# ip_phone_d_lcd_keyboard.net
KiCad netlist of a schematic drawn in Altium Designer
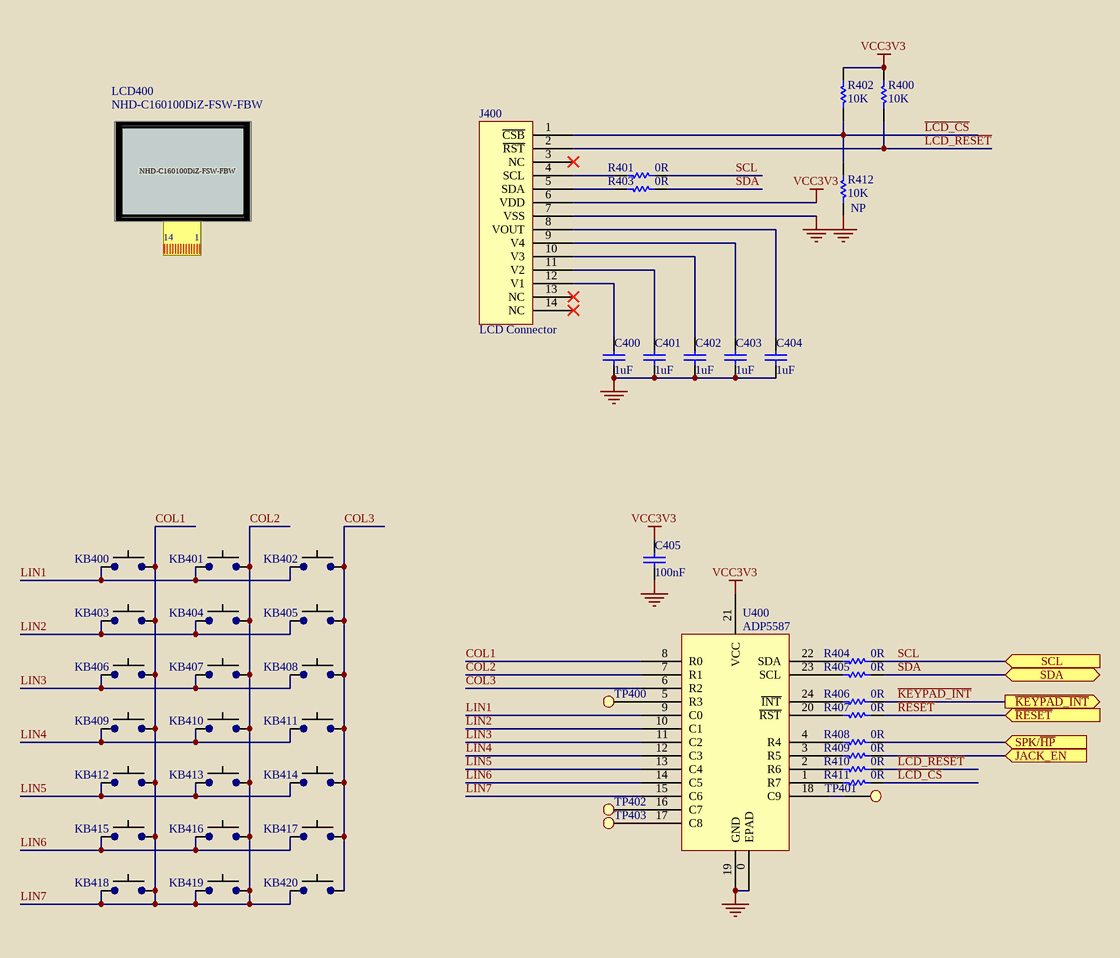
[diagram p0: ip_phone_d_lcd_keyboard.SchDoc]

(export (version "E")
  (design (tool "Eeschema 10.0.6"))
  (components
    (comp (ref "C400")
      (value "1uF")
      (footprint "ip_phone:CC1005-0402")
      (description "CAP CER 1.0UF 6.3V 20% X5R 0402")
      (fields
        (field (name "EVENDORPART#") "490-1319-1-ND")
        (field (name "MANUFACTURER") "Murata Electronics North America")
      )
      (libsource (lib "ip_phone") (part "Capacitor"))
    )
    (comp (ref "C401")
      (value "1uF")
      (footprint "ip_phone:CC1005-0402")
      (description "CAP CER 1.0UF 6.3V 20% X5R 0402")
      (fields
        (field (name "EVENDORPART#") "490-1319-1-ND")
        (field (name "MANUFACTURER") "Murata Electronics North America")
      )
      (libsource (lib "ip_phone") (part "Capacitor"))
    )
    (comp (ref "C402")
      (value "1uF")
      (footprint "ip_phone:CC1005-0402")
      (description "CAP CER 1.0UF 6.3V 20% X5R 0402")
      (fields
        (field (name "EVENDORPART#") "490-1319-1-ND")
        (field (name "MANUFACTURER") "Murata Electronics North America")
      )
      (libsource (lib "ip_phone") (part "Capacitor"))
    )
    (comp (ref "C403")
      (value "1uF")
      (footprint "ip_phone:CC1005-0402")
      (description "CAP CER 1.0UF 6.3V 20% X5R 0402")
      (fields
        (field (name "EVENDORPART#") "490-1319-1-ND")
        (field (name "MANUFACTURER") "Murata Electronics North America")
      )
      (libsource (lib "ip_phone") (part "Capacitor"))
    )
    (comp (ref "C404")
      (value "1uF")
      (footprint "ip_phone:CC1005-0402")
      (description "CAP CER 1.0UF 6.3V 20% X5R 0402")
      (fields
        (field (name "EVENDORPART#") "490-1319-1-ND")
        (field (name "MANUFACTURER") "Murata Electronics North America")
      )
      (libsource (lib "ip_phone") (part "Capacitor"))
    )
    (comp (ref "C405")
      (value "100nF")
      (footprint "ip_phone:CC1005-0402")
      (description "MLCC - SMD/SMT 0.1UF 16V 10% 0402")
      (fields (field (name "EVENDORPART#") "810-C1005X7R1C104K") (field (name "MANUFACTURER") "TDK"))
      (libsource (lib "ip_phone") (part "Capacitor"))
    )
    (comp (ref "J400")
      (value "LCD Connector")
      (footprint "ip_phone:LCD_Connector")
      (fields
        (field (name "EVENDORPART#") "538-52892-1495")
        (field (name "MANUFACTURER") "Molex")
        (field (name "PART#") "52892-1495")
      )
      (libsource (lib "ip_phone") (part "LCD Connector"))
    )
    (comp (ref "KB400")
      (value "Keypad_Button")
      (footprint "ip_phone:Keypad_Button")
      (libsource (lib "ip_phone") (part "Keypad_Button"))
    )
    (comp (ref "KB401")
      (value "Keypad_Button")
      (footprint "ip_phone:Keypad_Button")
      (libsource (lib "ip_phone") (part "Keypad_Button"))
    )
    (comp (ref "KB402")
      (value "Keypad_Button")
      (footprint "ip_phone:Keypad_Button")
      (libsource (lib "ip_phone") (part "Keypad_Button"))
    )
    (comp (ref "KB403")
      (value "Keypad_Button")
      (footprint "ip_phone:Keypad_Button")
      (libsource (lib "ip_phone") (part "Keypad_Button"))
    )
    (comp (ref "KB404")
      (value "Keypad_Button")
      (footprint "ip_phone:Keypad_Button")
      (libsource (lib "ip_phone") (part "Keypad_Button"))
    )
    (comp (ref "KB405")
      (value "Keypad_Button")
      (footprint "ip_phone:Keypad_Button")
      (libsource (lib "ip_phone") (part "Keypad_Button"))
    )
    (comp (ref "KB406")
      (value "Keypad_Button")
      (footprint "ip_phone:Keypad_Button")
      (libsource (lib "ip_phone") (part "Keypad_Button"))
    )
    (comp (ref "KB407")
      (value "Keypad_Button")
      (footprint "ip_phone:Keypad_Button")
      (libsource (lib "ip_phone") (part "Keypad_Button"))
    )
    (comp (ref "KB408")
      (value "Keypad_Button")
      (footprint "ip_phone:Keypad_Button")
      (libsource (lib "ip_phone") (part "Keypad_Button"))
    )
    (comp (ref "KB409")
      (value "Keypad_Button")
      (footprint "ip_phone:Keypad_Button")
      (libsource (lib "ip_phone") (part "Keypad_Button"))
    )
    (comp (ref "KB410")
      (value "Keypad_Button")
      (footprint "ip_phone:Keypad_Button")
      (libsource (lib "ip_phone") (part "Keypad_Button"))
    )
    (comp (ref "KB411")
      (value "Keypad_Button")
      (footprint "ip_phone:Keypad_Button")
      (libsource (lib "ip_phone") (part "Keypad_Button"))
    )
    (comp (ref "KB412")
      (value "Keypad_Button")
      (footprint "ip_phone:Keypad_Button")
      (libsource (lib "ip_phone") (part "Keypad_Button"))
    )
    (comp (ref "KB413")
      (value "Keypad_Button")
      (footprint "ip_phone:Keypad_Button")
      (libsource (lib "ip_phone") (part "Keypad_Button"))
    )
    (comp (ref "KB414")
      (value "Keypad_Button")
      (footprint "ip_phone:Keypad_Button")
      (libsource (lib "ip_phone") (part "Keypad_Button"))
    )
    (comp (ref "KB415")
      (value "Keypad_Button")
      (footprint "ip_phone:Keypad_Button")
      (libsource (lib "ip_phone") (part "Keypad_Button"))
    )
    (comp (ref "KB416")
      (value "Keypad_Button")
      (footprint "ip_phone:Keypad_Button")
      (libsource (lib "ip_phone") (part "Keypad_Button"))
    )
    (comp (ref "KB417")
      (value "Keypad_Button")
      (footprint "ip_phone:Keypad_Button")
      (libsource (lib "ip_phone") (part "Keypad_Button"))
    )
    (comp (ref "KB418")
      (value "Keypad_Button")
      (footprint "ip_phone:Keypad_Button")
      (libsource (lib "ip_phone") (part "Keypad_Button"))
    )
    (comp (ref "KB419")
      (value "Keypad_Button")
      (footprint "ip_phone:Keypad_Button")
      (libsource (lib "ip_phone") (part "Keypad_Button"))
    )
    (comp (ref "KB420")
      (value "Keypad_Button")
      (footprint "ip_phone:Keypad_Button")
      (libsource (lib "ip_phone") (part "Keypad_Button"))
    )
    (comp (ref "LCD400")
      (value "NHD-C160100DiZ-FSW-FBW")
      (description "LCD")
      (fields
        (field (name "EVENDORPART#") "763-C160100DIZFSWFBW")
        (field (name "MANUFACTURER") "Newhaven Display")
      )
      (libsource (lib "ip_phone") (part "LCD"))
    )
    (comp (ref "R400")
      (value "10K")
      (footprint "ip_phone:CR1005-0402")
      (description "Thick Film Resistors SMD 0402 10K 5%  1/16 W")
      (fields (field (name "EVENDORPART#") "311-10KJRCT-ND") (field (name "MANUFACTURER") "Yageo"))
      (libsource (lib "ip_phone") (part "Resistor"))
    )
    (comp (ref "R401")
      (value "0R")
      (footprint "ip_phone:CR1005-0402")
      (description "Thick Film Resistors 0402 1/16W Jumper")
      (fields
        (field (name "EVENDORPART#") "667-ERJ-2GE0R00X")
        (field (name "MANUFACTURER") "Panasonic Electronic Components")
      )
      (libsource (lib "ip_phone") (part "Resistor"))
    )
    (comp (ref "R402")
      (value "10K")
      (footprint "ip_phone:CR1005-0402")
      (description "Thick Film Resistors SMD 0402 10K 5%  1/16 W")
      (fields (field (name "EVENDORPART#") "311-10KJRCT-ND") (field (name "MANUFACTURER") "Yageo"))
      (libsource (lib "ip_phone") (part "Resistor"))
    )
    (comp (ref "R403")
      (value "0R")
      (footprint "ip_phone:CR1005-0402")
      (description "Thick Film Resistors 0402 1/16W Jumper")
      (fields
        (field (name "EVENDORPART#") "667-ERJ-2GE0R00X")
        (field (name "MANUFACTURER") "Panasonic Electronic Components")
      )
      (libsource (lib "ip_phone") (part "Resistor"))
    )
    (comp (ref "R404")
      (value "0R")
      (footprint "ip_phone:CR1005-0402")
      (description "Thick Film Resistors 0402 1/16W Jumper")
      (fields
        (field (name "EVENDORPART#") "667-ERJ-2GE0R00X")
        (field (name "MANUFACTURER") "Panasonic Electronic Components")
      )
      (libsource (lib "ip_phone") (part "Resistor"))
    )
    (comp (ref "R405")
      (value "0R")
      (footprint "ip_phone:CR1005-0402")
      (description "Thick Film Resistors 0402 1/16W Jumper")
      (fields
        (field (name "EVENDORPART#") "667-ERJ-2GE0R00X")
        (field (name "MANUFACTURER") "Panasonic Electronic Components")
      )
      (libsource (lib "ip_phone") (part "Resistor"))
    )
    (comp (ref "R406")
      (value "0R")
      (footprint "ip_phone:CR1005-0402")
      (description "Thick Film Resistors 0402 1/16W Jumper")
      (fields
        (field (name "EVENDORPART#") "667-ERJ-2GE0R00X")
        (field (name "MANUFACTURER") "Panasonic Electronic Components")
      )
      (libsource (lib "ip_phone") (part "Resistor"))
    )
    (comp (ref "R407")
      (value "0R")
      (footprint "ip_phone:CR1005-0402")
      (description "Thick Film Resistors 0402 1/16W Jumper")
      (fields
        (field (name "EVENDORPART#") "667-ERJ-2GE0R00X")
        (field (name "MANUFACTURER") "Panasonic Electronic Components")
      )
      (libsource (lib "ip_phone") (part "Resistor"))
    )
    (comp (ref "R408")
      (value "0R")
      (footprint "ip_phone:CR1005-0402")
      (description "Thick Film Resistors 0402 1/16W Jumper")
      (fields
        (field (name "EVENDORPART#") "667-ERJ-2GE0R00X")
        (field (name "MANUFACTURER") "Panasonic Electronic Components")
      )
      (libsource (lib "ip_phone") (part "Resistor"))
    )
    (comp (ref "R409")
      (value "0R")
      (footprint "ip_phone:CR1005-0402")
      (description "Thick Film Resistors 0402 1/16W Jumper")
      (fields
        (field (name "EVENDORPART#") "667-ERJ-2GE0R00X")
        (field (name "MANUFACTURER") "Panasonic Electronic Components")
      )
      (libsource (lib "ip_phone") (part "Resistor"))
    )
    (comp (ref "R410")
      (value "0R")
      (footprint "ip_phone:CR1005-0402")
      (description "Thick Film Resistors 0402 1/16W Jumper")
      (fields
        (field (name "EVENDORPART#") "667-ERJ-2GE0R00X")
        (field (name "MANUFACTURER") "Panasonic Electronic Components")
      )
      (libsource (lib "ip_phone") (part "Resistor"))
    )
    (comp (ref "R411")
      (value "0R")
      (footprint "ip_phone:CR1005-0402")
      (description "Thick Film Resistors 0402 1/16W Jumper")
      (fields
        (field (name "EVENDORPART#") "667-ERJ-2GE0R00X")
        (field (name "MANUFACTURER") "Panasonic Electronic Components")
      )
      (libsource (lib "ip_phone") (part "Resistor"))
    )
    (comp (ref "R412")
      (value "10K")
      (footprint "ip_phone:CR1005-0402")
      (description "Thick Film Resistors SMD 0402 10K 5%  1/16 W")
      (fields
        (field (name "EVENDORPART#") "311-10KJRCT-ND")
        (field (name "MANUFACTURER") "Yageo")
        (field (name "NP") "NP")
      )
      (libsource (lib "ip_phone") (part "Resistor"))
    )
    (comp (ref "TP400")
      (value "Test Point")
      (footprint "ip_phone:Test Point")
      (fields (field (name "EVENDORPART#") "NÃO SE APLICA"))
      (libsource (lib "ip_phone") (part "Test Point"))
    )
    (comp (ref "TP401")
      (value "Test Point")
      (footprint "ip_phone:Test Point")
      (fields (field (name "EVENDORPART#") "NÃO SE APLICA"))
      (libsource (lib "ip_phone") (part "Test Point"))
    )
    (comp (ref "TP402")
      (value "Test Point")
      (footprint "ip_phone:Test Point")
      (fields (field (name "EVENDORPART#") "NÃO SE APLICA"))
      (libsource (lib "ip_phone") (part "Test Point"))
    )
    (comp (ref "TP403")
      (value "Test Point")
      (footprint "ip_phone:Test Point")
      (fields (field (name "EVENDORPART#") "NÃO SE APLICA"))
      (libsource (lib "ip_phone") (part "Test Point"))
    )
    (comp (ref "U400")
      (value "ADP5587")
      (footprint "ip_phone:QFN-24")
      (description "IC Expander/Keyboard Controller")
      (fields (field (name "EVENDORPART#") "ADP5587ACPZ-R7CT-ND") (field (name "PART#") "ADP5587ACPZ-R7"))
      (libsource (lib "ip_phone") (part "ADP5587"))
    )
  )
  (nets
    (net (code "1") (name "/COL1") (class "Default")
      (node (ref "KB400") (pin "2") (pinfunction "2_2") (pintype "passive"))
      (node (ref "KB401") (pin "2") (pinfunction "2_2") (pintype "passive"))
      (node (ref "KB403") (pin "2") (pinfunction "2_2") (pintype "passive"))
      (node (ref "KB404") (pin "2") (pinfunction "2_2") (pintype "passive"))
      (node (ref "KB406") (pin "2") (pinfunction "2_2") (pintype "passive"))
      (node (ref "KB407") (pin "2") (pinfunction "2_2") (pintype "passive"))
      (node (ref "KB409") (pin "2") (pinfunction "2_2") (pintype "passive"))
      (node (ref "KB410") (pin "2") (pinfunction "2_2") (pintype "passive"))
      (node (ref "KB412") (pin "2") (pinfunction "2_2") (pintype "passive"))
      (node (ref "KB413") (pin "2") (pinfunction "2_2") (pintype "passive"))
      (node (ref "KB415") (pin "2") (pinfunction "2_2") (pintype "passive"))
      (node (ref "KB416") (pin "2") (pinfunction "2_2") (pintype "passive"))
      (node (ref "KB418") (pin "1") (pinfunction "1_1") (pintype "passive"))
      (node (ref "KB418") (pin "2") (pinfunction "2_2") (pintype "passive"))
      (node (ref "KB419") (pin "1") (pinfunction "1_1") (pintype "passive"))
      (node (ref "KB419") (pin "2") (pinfunction "2_2") (pintype "passive"))
      (node (ref "KB420") (pin "1") (pinfunction "1_1") (pintype "passive"))
      (node (ref "U400") (pin "15") (pinfunction "C6_15") (pintype "passive"))
      (node (ref "U400") (pin "7") (pinfunction "R1_7") (pintype "passive"))
      (node (ref "U400") (pin "8") (pinfunction "R0_8") (pintype "passive"))
    )
    (net (code "2") (name "/COL3") (class "Default")
      (node (ref "KB402") (pin "2") (pinfunction "2_2") (pintype "passive"))
      (node (ref "KB405") (pin "2") (pinfunction "2_2") (pintype "passive"))
      (node (ref "KB408") (pin "2") (pinfunction "2_2") (pintype "passive"))
      (node (ref "KB411") (pin "2") (pinfunction "2_2") (pintype "passive"))
      (node (ref "KB414") (pin "2") (pinfunction "2_2") (pintype "passive"))
      (node (ref "KB417") (pin "2") (pinfunction "2_2") (pintype "passive"))
      (node (ref "KB420") (pin "2") (pinfunction "2_2") (pintype "passive"))
      (node (ref "U400") (pin "6") (pinfunction "R2_6") (pintype "passive"))
    )
    (net (code "3") (name "/JACK_EN") (class "Default")
      (node (ref "R409") (pin "1") (pinfunction "1_1") (pintype "passive"))
    )
    (net (code "4") (name "/LIN1") (class "Default")
      (node (ref "KB400") (pin "1") (pinfunction "1_1") (pintype "passive"))
      (node (ref "KB401") (pin "1") (pinfunction "1_1") (pintype "passive"))
      (node (ref "KB402") (pin "1") (pinfunction "1_1") (pintype "passive"))
      (node (ref "U400") (pin "9") (pinfunction "C0_9") (pintype "passive"))
    )
    (net (code "5") (name "/LIN2") (class "Default")
      (node (ref "KB403") (pin "1") (pinfunction "1_1") (pintype "passive"))
      (node (ref "KB404") (pin "1") (pinfunction "1_1") (pintype "passive"))
      (node (ref "KB405") (pin "1") (pinfunction "1_1") (pintype "passive"))
      (node (ref "U400") (pin "10") (pinfunction "C1_10") (pintype "passive"))
    )
    (net (code "6") (name "/LIN3") (class "Default")
      (node (ref "KB406") (pin "1") (pinfunction "1_1") (pintype "passive"))
      (node (ref "KB407") (pin "1") (pinfunction "1_1") (pintype "passive"))
      (node (ref "KB408") (pin "1") (pinfunction "1_1") (pintype "passive"))
      (node (ref "U400") (pin "11") (pinfunction "C2_11") (pintype "passive"))
    )
    (net (code "7") (name "/LIN4") (class "Default")
      (node (ref "KB409") (pin "1") (pinfunction "1_1") (pintype "passive"))
      (node (ref "KB410") (pin "1") (pinfunction "1_1") (pintype "passive"))
      (node (ref "KB411") (pin "1") (pinfunction "1_1") (pintype "passive"))
      (node (ref "U400") (pin "12") (pinfunction "C3_12") (pintype "passive"))
    )
    (net (code "8") (name "/LIN5") (class "Default")
      (node (ref "KB412") (pin "1") (pinfunction "1_1") (pintype "passive"))
      (node (ref "KB413") (pin "1") (pinfunction "1_1") (pintype "passive"))
      (node (ref "KB414") (pin "1") (pinfunction "1_1") (pintype "passive"))
      (node (ref "U400") (pin "13") (pinfunction "C4_13") (pintype "passive"))
    )
    (net (code "9") (name "/LIN6") (class "Default")
      (node (ref "KB415") (pin "1") (pinfunction "1_1") (pintype "passive"))
      (node (ref "KB416") (pin "1") (pinfunction "1_1") (pintype "passive"))
      (node (ref "KB417") (pin "1") (pinfunction "1_1") (pintype "passive"))
      (node (ref "U400") (pin "14") (pinfunction "C5_14") (pintype "passive"))
    )
    (net (code "10") (name "/SCL") (class "Default")
      (node (ref "R401") (pin "1") (pinfunction "1_1") (pintype "passive"))
      (node (ref "R404") (pin "1") (pinfunction "1_1") (pintype "passive"))
    )
    (net (code "11") (name "/SDA") (class "Default")
      (node (ref "R403") (pin "1") (pinfunction "1_1") (pintype "passive"))
      (node (ref "R405") (pin "1") (pinfunction "1_1") (pintype "passive"))
    )
    (net (code "12") (name "/SPK{slash}~{HP}") (class "Default")
      (node (ref "R408") (pin "1") (pinfunction "1_1") (pintype "passive"))
    )
    (net (code "13") (name "/~{KEYPAD_INT}") (class "Default")
      (node (ref "R406") (pin "1") (pinfunction "1_1") (pintype "passive"))
    )
    (net (code "14") (name "/~{LCD_CS}") (class "Default")
      (node (ref "J400") (pin "1") (pinfunction "~{CSB}_1") (pintype "passive"))
      (node (ref "R402") (pin "1") (pinfunction "1_1") (pintype "passive"))
      (node (ref "R411") (pin "1") (pinfunction "1_1") (pintype "passive"))
      (node (ref "R412") (pin "2") (pinfunction "2_2") (pintype "passive"))
    )
    (net (code "15") (name "/~{LCD_RESET}") (class "Default")
      (node (ref "J400") (pin "2") (pinfunction "~{RST}_2") (pintype "passive"))
      (node (ref "R400") (pin "1") (pinfunction "1_1") (pintype "passive"))
      (node (ref "R410") (pin "1") (pinfunction "1_1") (pintype "passive"))
    )
    (net (code "16") (name "/~{RESET}") (class "Default")
      (node (ref "R407") (pin "1") (pinfunction "1_1") (pintype "passive"))
    )
    (net (code "17") (name "GND") (class "Default")
      (node (ref "C400") (pin "2") (pinfunction "2_2") (pintype "passive"))
      (node (ref "C401") (pin "2") (pinfunction "2_2") (pintype "passive"))
      (node (ref "C402") (pin "2") (pinfunction "2_2") (pintype "passive"))
      (node (ref "C403") (pin "2") (pinfunction "2_2") (pintype "passive"))
      (node (ref "C404") (pin "2") (pinfunction "2_2") (pintype "passive"))
      (node (ref "C405") (pin "1") (pinfunction "1_1") (pintype "passive"))
      (node (ref "J400") (pin "7") (pinfunction "VSS_7") (pintype "passive"))
      (node (ref "R412") (pin "1") (pinfunction "1_1") (pintype "passive"))
      (node (ref "U400") (pin "0") (pinfunction "EPAD_0") (pintype "passive"))
      (node (ref "U400") (pin "19") (pinfunction "GND_19") (pintype "passive"))
    )
    (net (code "18") (name "Net-(J400-SCL)") (class "Default")
      (node (ref "J400") (pin "4") (pinfunction "SCL_4") (pintype "passive"))
      (node (ref "R401") (pin "2") (pinfunction "2_2") (pintype "passive"))
    )
    (net (code "19") (name "Net-(J400-SDA)") (class "Default")
      (node (ref "J400") (pin "5") (pinfunction "SDA_5") (pintype "passive"))
      (node (ref "R403") (pin "2") (pinfunction "2_2") (pintype "passive"))
    )
    (net (code "20") (name "Net-(J400-V1)") (class "Default")
      (node (ref "C400") (pin "1") (pinfunction "1_1") (pintype "passive"))
      (node (ref "J400") (pin "12") (pinfunction "V1_12") (pintype "passive"))
    )
    (net (code "21") (name "Net-(J400-V2)") (class "Default")
      (node (ref "C401") (pin "1") (pinfunction "1_1") (pintype "passive"))
      (node (ref "J400") (pin "11") (pinfunction "V2_11") (pintype "passive"))
    )
    (net (code "22") (name "Net-(J400-V3)") (class "Default")
      (node (ref "C402") (pin "1") (pinfunction "1_1") (pintype "passive"))
      (node (ref "J400") (pin "10") (pinfunction "V3_10") (pintype "passive"))
    )
    (net (code "23") (name "Net-(J400-V4)") (class "Default")
      (node (ref "C403") (pin "1") (pinfunction "1_1") (pintype "passive"))
      (node (ref "J400") (pin "9") (pinfunction "V4_9") (pintype "passive"))
    )
    (net (code "24") (name "Net-(J400-VOUT)") (class "Default")
      (node (ref "C404") (pin "1") (pinfunction "1_1") (pintype "passive"))
      (node (ref "J400") (pin "8") (pinfunction "VOUT_8") (pintype "passive"))
    )
    (net (code "25") (name "Net-(U400-C7)") (class "Default")
      (node (ref "TP402") (pin "1") (pinfunction "1_1") (pintype "passive"))
      (node (ref "U400") (pin "16") (pinfunction "C7_16") (pintype "passive"))
    )
    (net (code "26") (name "Net-(U400-C8)") (class "Default")
      (node (ref "TP403") (pin "1") (pinfunction "1_1") (pintype "passive"))
      (node (ref "U400") (pin "17") (pinfunction "C8_17") (pintype "passive"))
    )
    (net (code "27") (name "Net-(U400-C9)") (class "Default")
      (node (ref "TP401") (pin "1") (pinfunction "1_1") (pintype "passive"))
      (node (ref "U400") (pin "18") (pinfunction "C9_18") (pintype "passive"))
    )
    (net (code "28") (name "Net-(U400-R3)") (class "Default")
      (node (ref "TP400") (pin "1") (pinfunction "1_1") (pintype "passive"))
      (node (ref "U400") (pin "5") (pinfunction "R3_5") (pintype "passive"))
    )
    (net (code "29") (name "Net-(U400-R4)") (class "Default")
      (node (ref "R408") (pin "2") (pinfunction "2_2") (pintype "passive"))
      (node (ref "U400") (pin "4") (pinfunction "R4_4") (pintype "passive"))
    )
    (net (code "30") (name "Net-(U400-R5)") (class "Default")
      (node (ref "R409") (pin "2") (pinfunction "2_2") (pintype "passive"))
      (node (ref "U400") (pin "3") (pinfunction "R5_3") (pintype "passive"))
    )
    (net (code "31") (name "Net-(U400-R6)") (class "Default")
      (node (ref "R410") (pin "2") (pinfunction "2_2") (pintype "passive"))
      (node (ref "U400") (pin "2") (pinfunction "R6_2") (pintype "passive"))
    )
    (net (code "32") (name "Net-(U400-R7)") (class "Default")
      (node (ref "R411") (pin "2") (pinfunction "2_2") (pintype "passive"))
      (node (ref "U400") (pin "1") (pinfunction "R7_1") (pintype "passive"))
    )
    (net (code "33") (name "Net-(U400-SCL)") (class "Default")
      (node (ref "R405") (pin "2") (pinfunction "2_2") (pintype "passive"))
      (node (ref "U400") (pin "23") (pinfunction "SCL_23") (pintype "passive"))
    )
    (net (code "34") (name "Net-(U400-SDA)") (class "Default")
      (node (ref "R404") (pin "2") (pinfunction "2_2") (pintype "passive"))
      (node (ref "U400") (pin "22") (pinfunction "SDA_22") (pintype "passive"))
    )
    (net (code "35") (name "Net-(U400-~{INT})") (class "Default")
      (node (ref "R406") (pin "2") (pinfunction "2_2") (pintype "passive"))
      (node (ref "U400") (pin "24") (pinfunction "~{INT}_24") (pintype "passive"))
    )
    (net (code "36") (name "Net-(U400-~{RST})") (class "Default")
      (node (ref "R407") (pin "2") (pinfunction "2_2") (pintype "passive"))
      (node (ref "U400") (pin "20") (pinfunction "~{RST}_20") (pintype "passive"))
    )
    (net (code "37") (name "VCC3V3") (class "Default")
      (node (ref "C405") (pin "2") (pinfunction "2_2") (pintype "passive"))
      (node (ref "J400") (pin "6") (pinfunction "VDD_6") (pintype "passive"))
      (node (ref "R400") (pin "2") (pinfunction "2_2") (pintype "passive"))
      (node (ref "R402") (pin "2") (pinfunction "2_2") (pintype "passive"))
      (node (ref "U400") (pin "21") (pinfunction "VCC_21") (pintype "passive"))
    )
    (net (code "38") (name "unconnected-(J400-NC-Pad3)") (class "Default")
      (node (ref "J400") (pin "3") (pinfunction "NC_3") (pintype "passive+no_connect"))
    )
    (net (code "39") (name "unconnected-(J400-NC-Pad13)") (class "Default")
      (node (ref "J400") (pin "13") (pinfunction "NC_13") (pintype "passive+no_connect"))
    )
    (net (code "40") (name "unconnected-(J400-NC-Pad14)") (class "Default")
      (node (ref "J400") (pin "14") (pinfunction "NC_14") (pintype "passive+no_connect"))
    )
  )
)
